# fat51p.net
KiCad netlist of a schematic drawn in Altium Designer
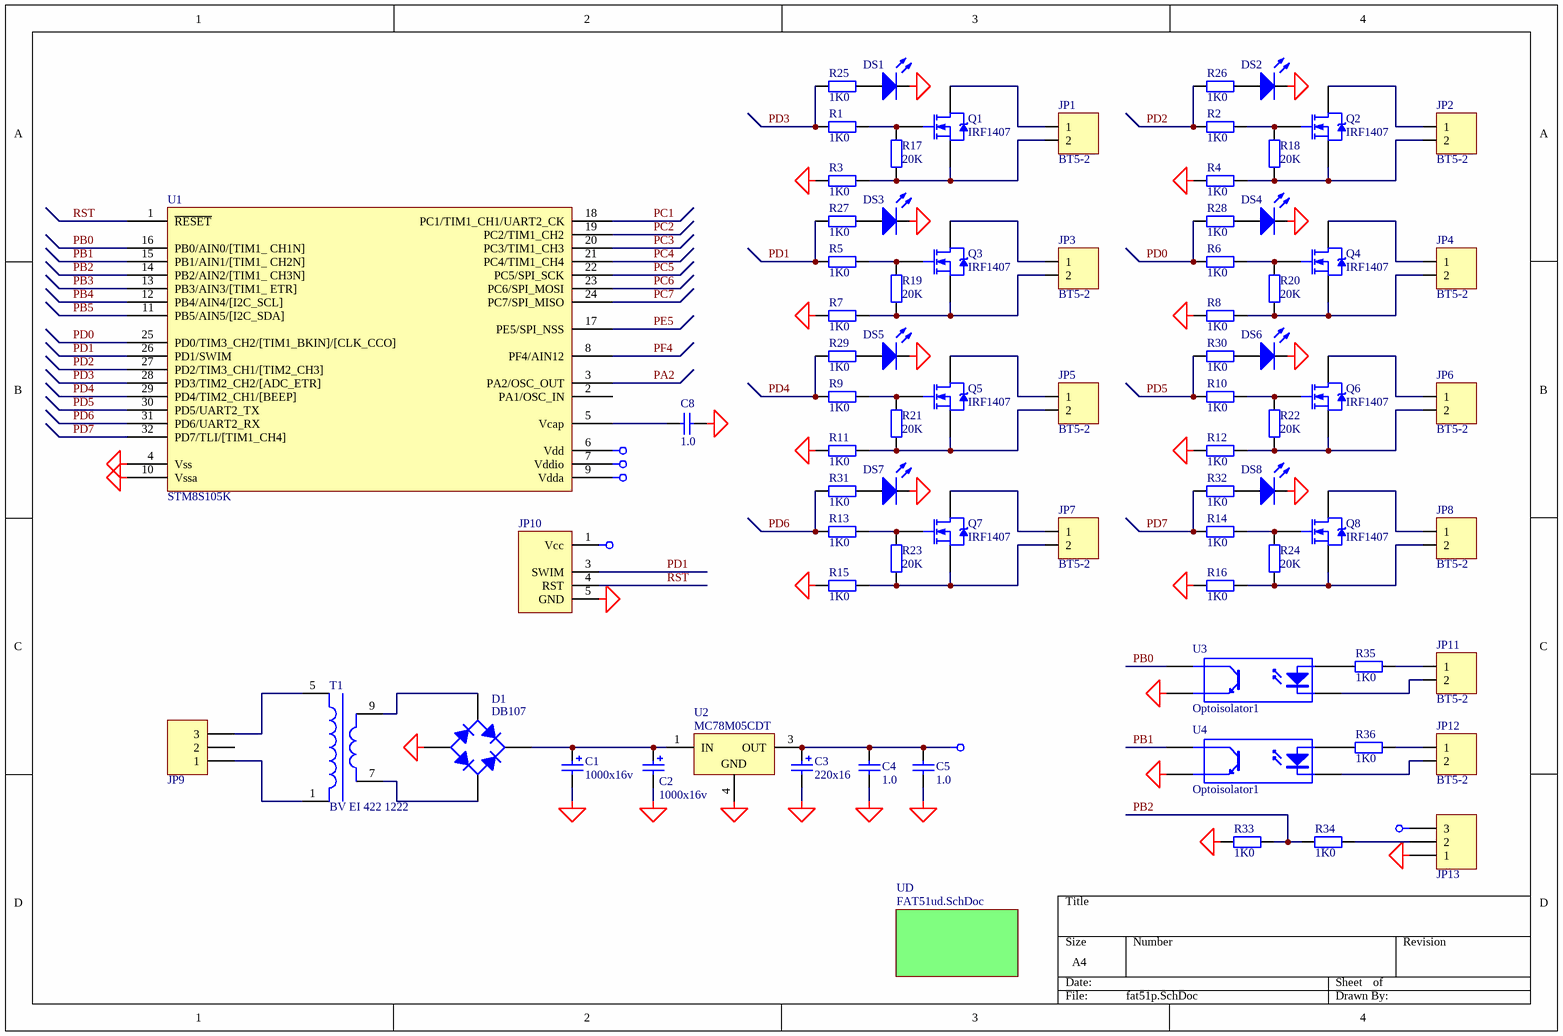
[diagram p0: fat51p.SchDoc]

(export (version "E")
  (design (tool "Eeschema 10.0.6"))
  (components
    (comp (ref "C1")
      (value "1000x16v")
      (footprint "el5")
      (description "Polarized Capacitor (Radial)")
      (fields (field (name "MANUFACTURER") "Generic Components") (field (name "PUBLISHER") "Altium Limited"))
      (libsource (lib "BUF") (part "Cap Pol1"))
    )
    (comp (ref "C2")
      (value "1000x16v")
      (footprint "el5")
      (description "Polarized Capacitor (Radial)")
      (fields (field (name "MANUFACTURER") "Generic Components") (field (name "PUBLISHER") "Altium Limited"))
      (libsource (lib "BUF") (part "Cap Pol1"))
    )
    (comp (ref "C3")
      (value "220x16")
      (footprint "el3")
      (description "Polarized Capacitor (Radial)")
      (fields (field (name "MANUFACTURER") "Generic Components") (field (name "PUBLISHER") "Altium Limited"))
      (libsource (lib "BUF") (part "Cap Pol"))
    )
    (comp (ref "C4")
      (value "Cap")
      (footprint "_1206")
      (description "Capacitor")
      (fields
        (field (name "MANUFACTURER") "Generic Components")
        (field (name "ALTIUM_VALUE") "1.0")
        (field (name "PUBLISHER") "Altium Limited")
      )
      (libsource (lib "BUF") (part "Cap"))
    )
    (comp (ref "C5")
      (value "Cap")
      (footprint "_1206")
      (description "Capacitor")
      (fields
        (field (name "MANUFACTURER") "Generic Components")
        (field (name "ALTIUM_VALUE") "1.0")
        (field (name "PUBLISHER") "Altium Limited")
      )
      (libsource (lib "BUF") (part "Cap"))
    )
    (comp (ref "C8")
      (value "1.0")
      (footprint "_1206")
      (description "Capacitor (Semiconductor SIM Model)")
      (fields (field (name "MANUFACTURER") "Generic Components") (field (name "PUBLISHER") "Altium Limited"))
      (libsource (lib "Miscellaneous Devices") (part "Cap Semi"))
    )
    (comp (ref "D1")
      (value "DB107")
      (footprint "DF01")
      (description "Full Wave Diode Bridge")
      (fields (field (name "MANUFACTURER") "Generic Components") (field (name "PUBLISHER") "Altium Limited"))
      (libsource (lib "Miscellaneous Devices") (part "Bridge1"))
    )
    (comp (ref "DS1")
      (value "LED0")
      (footprint "el3")
      (description "Typical INFRARED GaAs LED")
      (fields (field (name "MANUFACTURER") "Generic Components") (field (name "PUBLISHER") "Altium Limited"))
      (libsource (lib "PAL") (part "LED0"))
    )
    (comp (ref "DS2")
      (value "LED0")
      (footprint "el3")
      (description "Typical INFRARED GaAs LED")
      (fields (field (name "MANUFACTURER") "Generic Components") (field (name "PUBLISHER") "Altium Limited"))
      (libsource (lib "PAL") (part "LED0"))
    )
    (comp (ref "DS3")
      (value "LED0")
      (footprint "el3")
      (description "Typical INFRARED GaAs LED")
      (fields (field (name "MANUFACTURER") "Generic Components") (field (name "PUBLISHER") "Altium Limited"))
      (libsource (lib "PAL") (part "LED0"))
    )
    (comp (ref "DS4")
      (value "LED0")
      (footprint "el3")
      (description "Typical INFRARED GaAs LED")
      (fields (field (name "MANUFACTURER") "Generic Components") (field (name "PUBLISHER") "Altium Limited"))
      (libsource (lib "PAL") (part "LED0"))
    )
    (comp (ref "DS5")
      (value "LED0")
      (footprint "el3")
      (description "Typical INFRARED GaAs LED")
      (fields (field (name "MANUFACTURER") "Generic Components") (field (name "PUBLISHER") "Altium Limited"))
      (libsource (lib "PAL") (part "LED0"))
    )
    (comp (ref "DS6")
      (value "LED0")
      (footprint "el3")
      (description "Typical INFRARED GaAs LED")
      (fields (field (name "MANUFACTURER") "Generic Components") (field (name "PUBLISHER") "Altium Limited"))
      (libsource (lib "PAL") (part "LED0"))
    )
    (comp (ref "DS7")
      (value "LED0")
      (footprint "el3")
      (description "Typical INFRARED GaAs LED")
      (fields (field (name "MANUFACTURER") "Generic Components") (field (name "PUBLISHER") "Altium Limited"))
      (libsource (lib "PAL") (part "LED0"))
    )
    (comp (ref "DS8")
      (value "LED0")
      (footprint "el3")
      (description "Typical INFRARED GaAs LED")
      (fields (field (name "MANUFACTURER") "Generic Components") (field (name "PUBLISHER") "Altium Limited"))
      (libsource (lib "PAL") (part "LED0"))
    )
    (comp (ref "JP1")
      (value "BT5-2")
      (footprint "BT5-2-1")
      (description "Header, 3-Pin")
      (fields (field (name "MANUFACTURER") "Generic Components") (field (name "PUBLISHER") "Altium Limited"))
      (libsource (lib "PAL") (part "BT5-2"))
    )
    (comp (ref "JP2")
      (value "BT5-2")
      (footprint "BT5-2-1")
      (description "Header, 3-Pin")
      (fields (field (name "MANUFACTURER") "Generic Components") (field (name "PUBLISHER") "Altium Limited"))
      (libsource (lib "PAL") (part "BT5-2"))
    )
    (comp (ref "JP3")
      (value "BT5-2")
      (footprint "BT5-2-1")
      (description "Header, 3-Pin")
      (fields (field (name "MANUFACTURER") "Generic Components") (field (name "PUBLISHER") "Altium Limited"))
      (libsource (lib "PAL") (part "BT5-2"))
    )
    (comp (ref "JP4")
      (value "BT5-2")
      (footprint "BT5-2-1")
      (description "Header, 3-Pin")
      (fields (field (name "MANUFACTURER") "Generic Components") (field (name "PUBLISHER") "Altium Limited"))
      (libsource (lib "PAL") (part "BT5-2"))
    )
    (comp (ref "JP5")
      (value "BT5-2")
      (footprint "BT5-2-1")
      (description "Header, 3-Pin")
      (fields (field (name "MANUFACTURER") "Generic Components") (field (name "PUBLISHER") "Altium Limited"))
      (libsource (lib "PAL") (part "BT5-2"))
    )
    (comp (ref "JP6")
      (value "BT5-2")
      (footprint "BT5-2-1")
      (description "Header, 3-Pin")
      (fields (field (name "MANUFACTURER") "Generic Components") (field (name "PUBLISHER") "Altium Limited"))
      (libsource (lib "PAL") (part "BT5-2"))
    )
    (comp (ref "JP7")
      (value "BT5-2")
      (footprint "BT5-2-1")
      (description "Header, 3-Pin")
      (fields (field (name "MANUFACTURER") "Generic Components") (field (name "PUBLISHER") "Altium Limited"))
      (libsource (lib "PAL") (part "BT5-2"))
    )
    (comp (ref "JP8")
      (value "BT5-2")
      (footprint "BT5-2-1")
      (description "Header, 3-Pin")
      (fields (field (name "MANUFACTURER") "Generic Components") (field (name "PUBLISHER") "Altium Limited"))
      (libsource (lib "PAL") (part "BT5-2"))
    )
    (comp (ref "JP9")
      (value "Header 3")
      (footprint "BT5-3")
      (description "Header, 3-Pin")
      (fields (field (name "MANUFACTURER") "Generic Components") (field (name "PUBLISHER") "Altium Limited"))
      (libsource (lib "") (part "Header 3_1"))
    )
    (comp (ref "JP10") (value "~") (footprint "HDR1X5_uart") (libsource (lib "PAL") (part "SWIM_CONN")))
    (comp (ref "JP11")
      (value "BT5-2")
      (footprint "BT5-2-1")
      (description "Header, 3-Pin")
      (fields (field (name "MANUFACTURER") "Generic Components") (field (name "PUBLISHER") "Altium Limited"))
      (libsource (lib "PAL") (part "BT5-2"))
    )
    (comp (ref "JP12")
      (value "BT5-2")
      (footprint "BT5-2-1")
      (description "Header, 3-Pin")
      (fields (field (name "MANUFACTURER") "Generic Components") (field (name "PUBLISHER") "Altium Limited"))
      (libsource (lib "PAL") (part "BT5-2"))
    )
    (comp (ref "JP13")
      (value "Header 3")
      (footprint "BT5-3")
      (description "Header, 3-Pin")
      (fields (field (name "MANUFACTURER") "Generic Components") (field (name "PUBLISHER") "Altium Limited"))
      (libsource (lib "Miscellaneous Connectors") (part "Header 3"))
    )
    (comp (ref "Q1")
      (value "IRF1407")
      (footprint "7805_2")
      (description "HEXFET N-Channel Power MOSFET")
      (fields
        (field (name "MANUFACTURER") "International Rectifier")
        (field (name "PUBLISHER") "Altium Limited")
      )
      (libsource (lib "FAT51") (part "IRFR120"))
    )
    (comp (ref "Q2")
      (value "IRF1407")
      (footprint "7805_2")
      (description "HEXFET N-Channel Power MOSFET")
      (fields
        (field (name "MANUFACTURER") "International Rectifier")
        (field (name "PUBLISHER") "Altium Limited")
      )
      (libsource (lib "FAT51") (part "IRFR120"))
    )
    (comp (ref "Q3")
      (value "IRF1407")
      (footprint "7805_2")
      (description "HEXFET N-Channel Power MOSFET")
      (fields
        (field (name "MANUFACTURER") "International Rectifier")
        (field (name "PUBLISHER") "Altium Limited")
      )
      (libsource (lib "FAT51") (part "IRFR120"))
    )
    (comp (ref "Q4")
      (value "IRF1407")
      (footprint "7805_2")
      (description "HEXFET N-Channel Power MOSFET")
      (fields
        (field (name "MANUFACTURER") "International Rectifier")
        (field (name "PUBLISHER") "Altium Limited")
      )
      (libsource (lib "FAT51") (part "IRFR120"))
    )
    (comp (ref "Q5")
      (value "IRF1407")
      (footprint "7805_2")
      (description "HEXFET N-Channel Power MOSFET")
      (fields
        (field (name "MANUFACTURER") "International Rectifier")
        (field (name "PUBLISHER") "Altium Limited")
      )
      (libsource (lib "FAT51") (part "IRFR120"))
    )
    (comp (ref "Q6")
      (value "IRF1407")
      (footprint "7805_2")
      (description "HEXFET N-Channel Power MOSFET")
      (fields
        (field (name "MANUFACTURER") "International Rectifier")
        (field (name "PUBLISHER") "Altium Limited")
      )
      (libsource (lib "FAT51") (part "IRFR120"))
    )
    (comp (ref "Q7")
      (value "IRF1407")
      (footprint "7805_2")
      (description "HEXFET N-Channel Power MOSFET")
      (fields
        (field (name "MANUFACTURER") "International Rectifier")
        (field (name "PUBLISHER") "Altium Limited")
      )
      (libsource (lib "FAT51") (part "IRFR120"))
    )
    (comp (ref "Q8")
      (value "IRF1407")
      (footprint "7805_2")
      (description "HEXFET N-Channel Power MOSFET")
      (fields
        (field (name "MANUFACTURER") "International Rectifier")
        (field (name "PUBLISHER") "Altium Limited")
      )
      (libsource (lib "FAT51") (part "IRFR120"))
    )
    (comp (ref "R1")
      (value "1K0")
      (footprint "_1206")
      (description "Resistor")
      (fields (field (name "MANUFACTURER") "Generic Components") (field (name "PUBLISHER") "Altium Limited"))
      (libsource (lib "Miscellaneous Devices") (part "Res2"))
    )
    (comp (ref "R2")
      (value "1K0")
      (footprint "_1206")
      (description "Resistor")
      (fields (field (name "MANUFACTURER") "Generic Components") (field (name "PUBLISHER") "Altium Limited"))
      (libsource (lib "Miscellaneous Devices") (part "Res2"))
    )
    (comp (ref "R3")
      (value "1K0")
      (footprint "_1206")
      (description "Resistor")
      (fields (field (name "MANUFACTURER") "Generic Components") (field (name "PUBLISHER") "Altium Limited"))
      (libsource (lib "Miscellaneous Devices") (part "Res2"))
    )
    (comp (ref "R4")
      (value "1K0")
      (footprint "_1206")
      (description "Resistor")
      (fields (field (name "MANUFACTURER") "Generic Components") (field (name "PUBLISHER") "Altium Limited"))
      (libsource (lib "Miscellaneous Devices") (part "Res2"))
    )
    (comp (ref "R5")
      (value "1K0")
      (footprint "_1206")
      (description "Resistor")
      (fields (field (name "MANUFACTURER") "Generic Components") (field (name "PUBLISHER") "Altium Limited"))
      (libsource (lib "Miscellaneous Devices") (part "Res2"))
    )
    (comp (ref "R6")
      (value "1K0")
      (footprint "_1206")
      (description "Resistor")
      (fields (field (name "MANUFACTURER") "Generic Components") (field (name "PUBLISHER") "Altium Limited"))
      (libsource (lib "Miscellaneous Devices") (part "Res2"))
    )
    (comp (ref "R7")
      (value "1K0")
      (footprint "_1206")
      (description "Resistor")
      (fields (field (name "MANUFACTURER") "Generic Components") (field (name "PUBLISHER") "Altium Limited"))
      (libsource (lib "Miscellaneous Devices") (part "Res2"))
    )
    (comp (ref "R8")
      (value "1K0")
      (footprint "_1206")
      (description "Resistor")
      (fields (field (name "MANUFACTURER") "Generic Components") (field (name "PUBLISHER") "Altium Limited"))
      (libsource (lib "Miscellaneous Devices") (part "Res2"))
    )
    (comp (ref "R9")
      (value "1K0")
      (footprint "_1206")
      (description "Resistor")
      (fields (field (name "MANUFACTURER") "Generic Components") (field (name "PUBLISHER") "Altium Limited"))
      (libsource (lib "Miscellaneous Devices") (part "Res2"))
    )
    (comp (ref "R10")
      (value "1K0")
      (footprint "_1206")
      (description "Resistor")
      (fields (field (name "MANUFACTURER") "Generic Components") (field (name "PUBLISHER") "Altium Limited"))
      (libsource (lib "Miscellaneous Devices") (part "Res2"))
    )
    (comp (ref "R11")
      (value "1K0")
      (footprint "_1206")
      (description "Resistor")
      (fields (field (name "MANUFACTURER") "Generic Components") (field (name "PUBLISHER") "Altium Limited"))
      (libsource (lib "Miscellaneous Devices") (part "Res2"))
    )
    (comp (ref "R12")
      (value "1K0")
      (footprint "_1206")
      (description "Resistor")
      (fields (field (name "MANUFACTURER") "Generic Components") (field (name "PUBLISHER") "Altium Limited"))
      (libsource (lib "Miscellaneous Devices") (part "Res2"))
    )
    (comp (ref "R13")
      (value "1K0")
      (footprint "_1206")
      (description "Resistor")
      (fields (field (name "MANUFACTURER") "Generic Components") (field (name "PUBLISHER") "Altium Limited"))
      (libsource (lib "Miscellaneous Devices") (part "Res2"))
    )
    (comp (ref "R14")
      (value "1K0")
      (footprint "_1206")
      (description "Resistor")
      (fields (field (name "MANUFACTURER") "Generic Components") (field (name "PUBLISHER") "Altium Limited"))
      (libsource (lib "Miscellaneous Devices") (part "Res2"))
    )
    (comp (ref "R15")
      (value "1K0")
      (footprint "_1206")
      (description "Resistor")
      (fields (field (name "MANUFACTURER") "Generic Components") (field (name "PUBLISHER") "Altium Limited"))
      (libsource (lib "Miscellaneous Devices") (part "Res2"))
    )
    (comp (ref "R16")
      (value "1K0")
      (footprint "_1206")
      (description "Resistor")
      (fields (field (name "MANUFACTURER") "Generic Components") (field (name "PUBLISHER") "Altium Limited"))
      (libsource (lib "Miscellaneous Devices") (part "Res2"))
    )
    (comp (ref "R17")
      (value "20K")
      (footprint "_1206")
      (description "Resistor")
      (fields (field (name "MANUFACTURER") "Generic Components") (field (name "PUBLISHER") "Altium Limited"))
      (libsource (lib "") (part "Res2_1"))
    )
    (comp (ref "R18")
      (value "20K")
      (footprint "_1206")
      (description "Resistor")
      (fields (field (name "MANUFACTURER") "Generic Components") (field (name "PUBLISHER") "Altium Limited"))
      (libsource (lib "") (part "Res2_1"))
    )
    (comp (ref "R19")
      (value "20K")
      (footprint "_1206")
      (description "Resistor")
      (fields (field (name "MANUFACTURER") "Generic Components") (field (name "PUBLISHER") "Altium Limited"))
      (libsource (lib "") (part "Res2_1"))
    )
    (comp (ref "R20")
      (value "20K")
      (footprint "_1206")
      (description "Resistor")
      (fields (field (name "MANUFACTURER") "Generic Components") (field (name "PUBLISHER") "Altium Limited"))
      (libsource (lib "") (part "Res2_1"))
    )
    (comp (ref "R21")
      (value "20K")
      (footprint "_1206")
      (description "Resistor")
      (fields (field (name "MANUFACTURER") "Generic Components") (field (name "PUBLISHER") "Altium Limited"))
      (libsource (lib "") (part "Res2_1"))
    )
    (comp (ref "R22")
      (value "20K")
      (footprint "_1206")
      (description "Resistor")
      (fields (field (name "MANUFACTURER") "Generic Components") (field (name "PUBLISHER") "Altium Limited"))
      (libsource (lib "") (part "Res2_1"))
    )
    (comp (ref "R23")
      (value "20K")
      (footprint "_1206")
      (description "Resistor")
      (fields (field (name "MANUFACTURER") "Generic Components") (field (name "PUBLISHER") "Altium Limited"))
      (libsource (lib "") (part "Res2_1"))
    )
    (comp (ref "R24")
      (value "20K")
      (footprint "_1206")
      (description "Resistor")
      (fields (field (name "MANUFACTURER") "Generic Components") (field (name "PUBLISHER") "Altium Limited"))
      (libsource (lib "") (part "Res2_1"))
    )
    (comp (ref "R25")
      (value "1K0")
      (footprint "_1206")
      (description "Resistor")
      (fields (field (name "MANUFACTURER") "Generic Components") (field (name "PUBLISHER") "Altium Limited"))
      (libsource (lib "Miscellaneous Devices") (part "Res2"))
    )
    (comp (ref "R26")
      (value "1K0")
      (footprint "_1206")
      (description "Resistor")
      (fields (field (name "MANUFACTURER") "Generic Components") (field (name "PUBLISHER") "Altium Limited"))
      (libsource (lib "Miscellaneous Devices") (part "Res2"))
    )
    (comp (ref "R27")
      (value "1K0")
      (footprint "_1206")
      (description "Resistor")
      (fields (field (name "MANUFACTURER") "Generic Components") (field (name "PUBLISHER") "Altium Limited"))
      (libsource (lib "Miscellaneous Devices") (part "Res2"))
    )
    (comp (ref "R28")
      (value "1K0")
      (footprint "_1206")
      (description "Resistor")
      (fields (field (name "MANUFACTURER") "Generic Components") (field (name "PUBLISHER") "Altium Limited"))
      (libsource (lib "Miscellaneous Devices") (part "Res2"))
    )
    (comp (ref "R29")
      (value "1K0")
      (footprint "_1206")
      (description "Resistor")
      (fields (field (name "MANUFACTURER") "Generic Components") (field (name "PUBLISHER") "Altium Limited"))
      (libsource (lib "Miscellaneous Devices") (part "Res2"))
    )
    (comp (ref "R30")
      (value "1K0")
      (footprint "_1206")
      (description "Resistor")
      (fields (field (name "MANUFACTURER") "Generic Components") (field (name "PUBLISHER") "Altium Limited"))
      (libsource (lib "Miscellaneous Devices") (part "Res2"))
    )
    (comp (ref "R31")
      (value "1K0")
      (footprint "_1206")
      (description "Resistor")
      (fields (field (name "MANUFACTURER") "Generic Components") (field (name "PUBLISHER") "Altium Limited"))
      (libsource (lib "Miscellaneous Devices") (part "Res2"))
    )
    (comp (ref "R32")
      (value "1K0")
      (footprint "_1206")
      (description "Resistor")
      (fields (field (name "MANUFACTURER") "Generic Components") (field (name "PUBLISHER") "Altium Limited"))
      (libsource (lib "Miscellaneous Devices") (part "Res2"))
    )
    (comp (ref "R33")
      (value "1K0")
      (footprint "_1206")
      (description "Resistor")
      (fields (field (name "MANUFACTURER") "Generic Components") (field (name "PUBLISHER") "Altium Limited"))
      (libsource (lib "Miscellaneous Devices") (part "Res2"))
    )
    (comp (ref "R34")
      (value "1K0")
      (footprint "_1206")
      (description "Resistor")
      (fields (field (name "MANUFACTURER") "Generic Components") (field (name "PUBLISHER") "Altium Limited"))
      (libsource (lib "Miscellaneous Devices") (part "Res2"))
    )
    (comp (ref "R35")
      (value "1K0")
      (footprint "_1206")
      (description "Resistor")
      (fields (field (name "MANUFACTURER") "Generic Components") (field (name "PUBLISHER") "Altium Limited"))
      (libsource (lib "Miscellaneous Devices") (part "Res2"))
    )
    (comp (ref "R36")
      (value "1K0")
      (footprint "_1206")
      (description "Resistor")
      (fields (field (name "MANUFACTURER") "Generic Components") (field (name "PUBLISHER") "Altium Limited"))
      (libsource (lib "Miscellaneous Devices") (part "Res2"))
    )
    (comp (ref "T1")
      (value "BV EI 422 1222")
      (footprint "BV EI 422 1226_L")
      (fields (field (name "MANUFACTURER") "Generic Components") (field (name "PUBLISHER") "Altium Limited"))
      (libsource (lib "PAL") (part "BV EI 302"))
    )
    (comp (ref "U1")
      (value "STM8S105K")
      (footprint "QFP7X7-G32/X.5N")
      (libsource (lib "PAL") (part "STM8S105K"))
    )
    (comp (ref "U2")
      (value "MC78M05CDT")
      (footprint "SIP-G3/Z11.05")
      (description "Three-Terminal Medium Current Positive Voltage Regulator")
      (fields (field (name "MANUFACTURER") "ON Semiconductor") (field (name "PUBLISHER") "Altium Limited"))
      (libsource (lib "ON Semi Power Mgt Voltage Regulator") (part "MC78M05CDT"))
    )
    (comp (ref "U3")
      (value "Optoisolator1")
      (footprint "SO-G4")
      (description "Optoisolator")
      (fields (field (name "MANUFACTURER") "Generic Components") (field (name "PUBLISHER") "Altium Limited"))
      (libsource (lib "PAL") (part "Optoisolator1"))
    )
    (comp (ref "U4")
      (value "Optoisolator1")
      (footprint "SO-G4")
      (description "Optoisolator")
      (fields (field (name "MANUFACTURER") "Generic Components") (field (name "PUBLISHER") "Altium Limited"))
      (libsource (lib "PAL") (part "Optoisolator1"))
    )
  )
  (nets
    (net (code "1") (name "+5v") (class "Default")
      (node (ref "C3") (pin "1") (pinfunction "1_1") (pintype "passive"))
      (node (ref "C4") (pin "2") (pinfunction "2_2") (pintype "passive"))
      (node (ref "C5") (pin "2") (pinfunction "2_2") (pintype "passive"))
      (node (ref "JP10") (pin "1") (pinfunction "Vcc_1") (pintype "passive"))
      (node (ref "JP13") (pin "3") (pinfunction "3_3") (pintype "passive"))
      (node (ref "U1") (pin "6") (pinfunction "Vdd_6") (pintype "passive"))
      (node (ref "U1") (pin "7") (pinfunction "Vddio_7") (pintype "passive"))
      (node (ref "U1") (pin "9") (pinfunction "Vdda_9") (pintype "passive"))
      (node (ref "U2") (pin "3") (pinfunction "OUT_3") (pintype "power_in"))
    )
    (net (code "2") (name "/PA2") (class "Default")
      (node (ref "U1") (pin "3") (pinfunction "PA2/OSC_OUT_3") (pintype "passive"))
    )
    (net (code "3") (name "/PB0") (class "Default")
      (node (ref "U1") (pin "16") (pinfunction "PB0/AIN0/[TIM1__CH1N]_16") (pintype "passive"))
      (node (ref "U3") (pin "4") (pinfunction "C_4") (pintype "passive"))
    )
    (net (code "4") (name "/PB1") (class "Default")
      (node (ref "U1") (pin "15") (pinfunction "PB1/AIN1/[TIM1__CH2N]_15") (pintype "passive"))
      (node (ref "U4") (pin "4") (pinfunction "C_4") (pintype "passive"))
    )
    (net (code "5") (name "/PB2") (class "Default")
      (node (ref "R33") (pin "2") (pinfunction "2_2") (pintype "passive"))
      (node (ref "R34") (pin "1") (pinfunction "1_1") (pintype "passive"))
      (node (ref "U1") (pin "14") (pinfunction "PB2/AIN2/[TIM1__CH3N]_14") (pintype "passive"))
    )
    (net (code "6") (name "/PB3") (class "Default")
      (node (ref "U1") (pin "13") (pinfunction "PB3/AIN3/[TIM1__ETR]_13") (pintype "passive"))
    )
    (net (code "7") (name "/PB4") (class "Default")
      (node (ref "U1") (pin "12") (pinfunction "PB4/AIN4/[I2C_SCL]_12") (pintype "passive"))
    )
    (net (code "8") (name "/PB5") (class "Default")
      (node (ref "U1") (pin "11") (pinfunction "PB5/AIN5/[I2C_SDA]_11") (pintype "passive"))
    )
    (net (code "9") (name "/PC1") (class "Default")
      (node (ref "U1") (pin "18") (pinfunction "PC1/TIM1_CH1/UART2_CK_18") (pintype "passive"))
    )
    (net (code "10") (name "/PC2") (class "Default")
      (node (ref "U1") (pin "19") (pinfunction "PC2/TIM1_CH2_19") (pintype "passive"))
    )
    (net (code "11") (name "/PC3") (class "Default")
      (node (ref "U1") (pin "20") (pinfunction "PC3/TIM1_CH3_20") (pintype "passive"))
    )
    (net (code "12") (name "/PC4") (class "Default")
      (node (ref "U1") (pin "21") (pinfunction "PC4/TIM1_CH4_21") (pintype "passive"))
    )
    (net (code "13") (name "/PC5") (class "Default")
      (node (ref "U1") (pin "22") (pinfunction "PC5/SPI_SCK_22") (pintype "passive"))
    )
    (net (code "14") (name "/PC6") (class "Default")
      (node (ref "U1") (pin "23") (pinfunction "PC6/SPI_MOSI_23") (pintype "passive"))
    )
    (net (code "15") (name "/PC7") (class "Default")
      (node (ref "U1") (pin "24") (pinfunction "PC7/SPI_MISO_24") (pintype "passive"))
    )
    (net (code "16") (name "/PD0") (class "Default")
      (node (ref "R28") (pin "1") (pinfunction "1_1") (pintype "passive"))
      (node (ref "R6") (pin "1") (pinfunction "1_1") (pintype "passive"))
      (node (ref "U1") (pin "25") (pinfunction "PD0/TIM3_CH2/[TIM1_BKIN]/[CLK_CCO]_25") (pintype "passive"))
    )
    (net (code "17") (name "/PD1") (class "Default")
      (node (ref "JP10") (pin "3") (pinfunction "SWIM_3") (pintype "passive"))
      (node (ref "R27") (pin "1") (pinfunction "1_1") (pintype "passive"))
      (node (ref "R5") (pin "1") (pinfunction "1_1") (pintype "passive"))
      (node (ref "U1") (pin "26") (pinfunction "PD1/SWIM_26") (pintype "passive"))
    )
    (net (code "18") (name "/PD2") (class "Default")
      (node (ref "R2") (pin "1") (pinfunction "1_1") (pintype "passive"))
      (node (ref "R26") (pin "1") (pinfunction "1_1") (pintype "passive"))
      (node (ref "U1") (pin "27") (pinfunction "PD2/TIM3_CH1/[TIM2_CH3]_27") (pintype "passive"))
    )
    (net (code "19") (name "/PD3") (class "Default")
      (node (ref "R1") (pin "1") (pinfunction "1_1") (pintype "passive"))
      (node (ref "R25") (pin "1") (pinfunction "1_1") (pintype "passive"))
      (node (ref "U1") (pin "28") (pinfunction "PD3/TIM2_CH2/[ADC_ETR]_28") (pintype "passive"))
    )
    (net (code "20") (name "/PD4") (class "Default")
      (node (ref "R29") (pin "1") (pinfunction "1_1") (pintype "passive"))
      (node (ref "R9") (pin "1") (pinfunction "1_1") (pintype "passive"))
      (node (ref "U1") (pin "29") (pinfunction "PD4/TIM2_CH1/[BEEP]_29") (pintype "passive"))
    )
    (net (code "21") (name "/PD5") (class "Default")
      (node (ref "R10") (pin "1") (pinfunction "1_1") (pintype "passive"))
      (node (ref "R30") (pin "1") (pinfunction "1_1") (pintype "passive"))
      (node (ref "U1") (pin "30") (pinfunction "PD5/UART2_TX_30") (pintype "passive"))
    )
    (net (code "22") (name "/PD6") (class "Default")
      (node (ref "R13") (pin "1") (pinfunction "1_1") (pintype "passive"))
      (node (ref "R31") (pin "1") (pinfunction "1_1") (pintype "passive"))
      (node (ref "U1") (pin "31") (pinfunction "PD6/UART2_RX_31") (pintype "passive"))
    )
    (net (code "23") (name "/PD7") (class "Default")
      (node (ref "R14") (pin "1") (pinfunction "1_1") (pintype "passive"))
      (node (ref "R32") (pin "1") (pinfunction "1_1") (pintype "passive"))
      (node (ref "U1") (pin "32") (pinfunction "PD7/TLI/[TIM1_CH4]_32") (pintype "passive"))
    )
    (net (code "24") (name "/PE5") (class "Default")
      (node (ref "U1") (pin "17") (pinfunction "PE5/SPI_NSS_17") (pintype "passive"))
    )
    (net (code "25") (name "/PF4") (class "Default")
      (node (ref "U1") (pin "8") (pinfunction "PF4/AIN12_8") (pintype "passive"))
    )
    (net (code "26") (name "/RST") (class "Default")
      (node (ref "JP10") (pin "4") (pinfunction "RST_4") (pintype "passive"))
      (node (ref "U1") (pin "1") (pinfunction "~{RESET}_1") (pintype "passive"))
    )
    (net (code "27") (name "GND") (class "Default")
      (node (ref "C1") (pin "2") (pinfunction "2_2") (pintype "passive"))
      (node (ref "C2") (pin "2") (pinfunction "2_2") (pintype "passive"))
      (node (ref "C3") (pin "2") (pinfunction "2_2") (pintype "passive"))
      (node (ref "C4") (pin "1") (pinfunction "1_1") (pintype "passive"))
      (node (ref "C5") (pin "1") (pinfunction "1_1") (pintype "passive"))
      (node (ref "C8") (pin "1") (pinfunction "1_1") (pintype "passive"))
      (node (ref "D1") (pin "1") (pinfunction "A_1") (pintype "passive"))
      (node (ref "DS1") (pin "2") (pinfunction "K_2") (pintype "passive"))
      (node (ref "DS2") (pin "2") (pinfunction "K_2") (pintype "passive"))
      (node (ref "DS3") (pin "2") (pinfunction "K_2") (pintype "passive"))
      (node (ref "DS4") (pin "2") (pinfunction "K_2") (pintype "passive"))
      (node (ref "DS5") (pin "2") (pinfunction "K_2") (pintype "passive"))
      (node (ref "DS6") (pin "2") (pinfunction "K_2") (pintype "passive"))
      (node (ref "DS7") (pin "2") (pinfunction "K_2") (pintype "passive"))
      (node (ref "DS8") (pin "2") (pinfunction "K_2") (pintype "passive"))
      (node (ref "JP10") (pin "5") (pinfunction "GND_5") (pintype "passive"))
      (node (ref "JP13") (pin "1") (pinfunction "1_1") (pintype "passive"))
      (node (ref "R11") (pin "1") (pinfunction "1_1") (pintype "passive"))
      (node (ref "R12") (pin "1") (pinfunction "1_1") (pintype "passive"))
      (node (ref "R15") (pin "1") (pinfunction "1_1") (pintype "passive"))
      (node (ref "R16") (pin "1") (pinfunction "1_1") (pintype "passive"))
      (node (ref "R3") (pin "1") (pinfunction "1_1") (pintype "passive"))
      (node (ref "R33") (pin "1") (pinfunction "1_1") (pintype "passive"))
      (node (ref "R4") (pin "1") (pinfunction "1_1") (pintype "passive"))
      (node (ref "R7") (pin "1") (pinfunction "1_1") (pintype "passive"))
      (node (ref "R8") (pin "1") (pinfunction "1_1") (pintype "passive"))
      (node (ref "U1") (pin "10") (pinfunction "Vssa_10") (pintype "passive"))
      (node (ref "U1") (pin "4") (pinfunction "Vss_4") (pintype "passive"))
      (node (ref "U2") (pin "4") (pinfunction "GND_4") (pintype "power_in"))
      (node (ref "U3") (pin "3") (pinfunction "E_3") (pintype "passive"))
      (node (ref "U4") (pin "3") (pinfunction "E_3") (pintype "passive"))
    )
    (net (code "28") (name "Net-(D1-K)") (class "Default")
      (node (ref "C1") (pin "1") (pinfunction "1_1") (pintype "passive"))
      (node (ref "C2") (pin "1") (pinfunction "1_1") (pintype "passive"))
      (node (ref "D1") (pin "3") (pinfunction "K_3") (pintype "passive"))
      (node (ref "U2") (pin "1") (pinfunction "IN_1") (pintype "power_in"))
    )
    (net (code "29") (name "Net-(DS1-A)") (class "Default")
      (node (ref "DS1") (pin "1") (pinfunction "A_1") (pintype "passive"))
      (node (ref "R25") (pin "2") (pinfunction "2_2") (pintype "passive"))
    )
    (net (code "30") (name "Net-(DS2-A)") (class "Default")
      (node (ref "DS2") (pin "1") (pinfunction "A_1") (pintype "passive"))
      (node (ref "R26") (pin "2") (pinfunction "2_2") (pintype "passive"))
    )
    (net (code "31") (name "Net-(DS3-A)") (class "Default")
      (node (ref "DS3") (pin "1") (pinfunction "A_1") (pintype "passive"))
      (node (ref "R27") (pin "2") (pinfunction "2_2") (pintype "passive"))
    )
    (net (code "32") (name "Net-(DS4-A)") (class "Default")
      (node (ref "DS4") (pin "1") (pinfunction "A_1") (pintype "passive"))
      (node (ref "R28") (pin "2") (pinfunction "2_2") (pintype "passive"))
    )
    (net (code "33") (name "Net-(DS5-A)") (class "Default")
      (node (ref "DS5") (pin "1") (pinfunction "A_1") (pintype "passive"))
      (node (ref "R29") (pin "2") (pinfunction "2_2") (pintype "passive"))
    )
    (net (code "34") (name "Net-(DS6-A)") (class "Default")
      (node (ref "DS6") (pin "1") (pinfunction "A_1") (pintype "passive"))
      (node (ref "R30") (pin "2") (pinfunction "2_2") (pintype "passive"))
    )
    (net (code "35") (name "Net-(DS7-A)") (class "Default")
      (node (ref "DS7") (pin "1") (pinfunction "A_1") (pintype "passive"))
      (node (ref "R31") (pin "2") (pinfunction "2_2") (pintype "passive"))
    )
    (net (code "36") (name "Net-(DS8-A)") (class "Default")
      (node (ref "DS8") (pin "1") (pinfunction "A_1") (pintype "passive"))
      (node (ref "R32") (pin "2") (pinfunction "2_2") (pintype "passive"))
    )
    (net (code "37") (name "Net-(JP11-Pad1)") (class "Default")
      (node (ref "JP11") (pin "1") (pinfunction "1_1") (pintype "passive"))
      (node (ref "R35") (pin "2") (pinfunction "2_2") (pintype "passive"))
    )
    (net (code "38") (name "Net-(JP12-Pad1)") (class "Default")
      (node (ref "JP12") (pin "1") (pinfunction "1_1") (pintype "passive"))
      (node (ref "R36") (pin "2") (pinfunction "2_2") (pintype "passive"))
    )
    (net (code "39") (name "Net-(JP13-Pad2)") (class "Default")
      (node (ref "JP13") (pin "2") (pinfunction "2_2") (pintype "passive"))
      (node (ref "R34") (pin "2") (pinfunction "2_2") (pintype "passive"))
    )
    (net (code "40") (name "Net-(Q1-D)") (class "Default")
      (node (ref "JP1") (pin "1") (pinfunction "1_1") (pintype "passive"))
      (node (ref "Q1") (pin "2") (pinfunction "D_2") (pintype "passive"))
    )
    (net (code "41") (name "Net-(Q1-G)") (class "Default")
      (node (ref "Q1") (pin "1") (pinfunction "G_1") (pintype "passive"))
      (node (ref "R1") (pin "2") (pinfunction "2_2") (pintype "passive"))
      (node (ref "R17") (pin "1") (pinfunction "1_1") (pintype "passive"))
    )
    (net (code "42") (name "Net-(Q1-S)") (class "Default")
      (node (ref "JP1") (pin "2") (pinfunction "2_2") (pintype "passive"))
      (node (ref "Q1") (pin "3") (pinfunction "S_3") (pintype "passive"))
      (node (ref "R17") (pin "2") (pinfunction "2_2") (pintype "passive"))
      (node (ref "R3") (pin "2") (pinfunction "2_2") (pintype "passive"))
    )
    (net (code "43") (name "Net-(Q2-D)") (class "Default")
      (node (ref "JP2") (pin "1") (pinfunction "1_1") (pintype "passive"))
      (node (ref "Q2") (pin "2") (pinfunction "D_2") (pintype "passive"))
    )
    (net (code "44") (name "Net-(Q2-G)") (class "Default")
      (node (ref "Q2") (pin "1") (pinfunction "G_1") (pintype "passive"))
      (node (ref "R18") (pin "1") (pinfunction "1_1") (pintype "passive"))
      (node (ref "R2") (pin "2") (pinfunction "2_2") (pintype "passive"))
    )
    (net (code "45") (name "Net-(Q2-S)") (class "Default")
      (node (ref "JP2") (pin "2") (pinfunction "2_2") (pintype "passive"))
      (node (ref "Q2") (pin "3") (pinfunction "S_3") (pintype "passive"))
      (node (ref "R18") (pin "2") (pinfunction "2_2") (pintype "passive"))
      (node (ref "R4") (pin "2") (pinfunction "2_2") (pintype "passive"))
    )
    (net (code "46") (name "Net-(Q3-D)") (class "Default")
      (node (ref "JP3") (pin "1") (pinfunction "1_1") (pintype "passive"))
      (node (ref "Q3") (pin "2") (pinfunction "D_2") (pintype "passive"))
    )
    (net (code "47") (name "Net-(Q3-G)") (class "Default")
      (node (ref "Q3") (pin "1") (pinfunction "G_1") (pintype "passive"))
      (node (ref "R19") (pin "1") (pinfunction "1_1") (pintype "passive"))
      (node (ref "R5") (pin "2") (pinfunction "2_2") (pintype "passive"))
    )
    (net (code "48") (name "Net-(Q3-S)") (class "Default")
      (node (ref "JP3") (pin "2") (pinfunction "2_2") (pintype "passive"))
      (node (ref "Q3") (pin "3") (pinfunction "S_3") (pintype "passive"))
      (node (ref "R19") (pin "2") (pinfunction "2_2") (pintype "passive"))
      (node (ref "R7") (pin "2") (pinfunction "2_2") (pintype "passive"))
    )
    (net (code "49") (name "Net-(Q4-D)") (class "Default")
      (node (ref "JP4") (pin "1") (pinfunction "1_1") (pintype "passive"))
      (node (ref "Q4") (pin "2") (pinfunction "D_2") (pintype "passive"))
    )
    (net (code "50") (name "Net-(Q4-G)") (class "Default")
      (node (ref "Q4") (pin "1") (pinfunction "G_1") (pintype "passive"))
      (node (ref "R20") (pin "1") (pinfunction "1_1") (pintype "passive"))
      (node (ref "R6") (pin "2") (pinfunction "2_2") (pintype "passive"))
    )
    (net (code "51") (name "Net-(Q4-S)") (class "Default")
      (node (ref "JP4") (pin "2") (pinfunction "2_2") (pintype "passive"))
      (node (ref "Q4") (pin "3") (pinfunction "S_3") (pintype "passive"))
      (node (ref "R20") (pin "2") (pinfunction "2_2") (pintype "passive"))
      (node (ref "R8") (pin "2") (pinfunction "2_2") (pintype "passive"))
    )
    (net (code "52") (name "Net-(Q5-D)") (class "Default")
      (node (ref "JP5") (pin "1") (pinfunction "1_1") (pintype "passive"))
      (node (ref "Q5") (pin "2") (pinfunction "D_2") (pintype "passive"))
    )
    (net (code "53") (name "Net-(Q5-G)") (class "Default")
      (node (ref "Q5") (pin "1") (pinfunction "G_1") (pintype "passive"))
      (node (ref "R21") (pin "1") (pinfunction "1_1") (pintype "passive"))
      (node (ref "R9") (pin "2") (pinfunction "2_2") (pintype "passive"))
    )
    (net (code "54") (name "Net-(Q5-S)") (class "Default")
      (node (ref "JP5") (pin "2") (pinfunction "2_2") (pintype "passive"))
      (node (ref "Q5") (pin "3") (pinfunction "S_3") (pintype "passive"))
      (node (ref "R11") (pin "2") (pinfunction "2_2") (pintype "passive"))
      (node (ref "R21") (pin "2") (pinfunction "2_2") (pintype "passive"))
    )
    (net (code "55") (name "Net-(Q6-D)") (class "Default")
      (node (ref "JP6") (pin "1") (pinfunction "1_1") (pintype "passive"))
      (node (ref "Q6") (pin "2") (pinfunction "D_2") (pintype "passive"))
    )
    (net (code "56") (name "Net-(Q6-G)") (class "Default")
      (node (ref "Q6") (pin "1") (pinfunction "G_1") (pintype "passive"))
      (node (ref "R10") (pin "2") (pinfunction "2_2") (pintype "passive"))
      (node (ref "R22") (pin "1") (pinfunction "1_1") (pintype "passive"))
    )
    (net (code "57") (name "Net-(Q6-S)") (class "Default")
      (node (ref "JP6") (pin "2") (pinfunction "2_2") (pintype "passive"))
      (node (ref "Q6") (pin "3") (pinfunction "S_3") (pintype "passive"))
      (node (ref "R12") (pin "2") (pinfunction "2_2") (pintype "passive"))
      (node (ref "R22") (pin "2") (pinfunction "2_2") (pintype "passive"))
    )
    (net (code "58") (name "Net-(Q7-D)") (class "Default")
      (node (ref "JP7") (pin "1") (pinfunction "1_1") (pintype "passive"))
      (node (ref "Q7") (pin "2") (pinfunction "D_2") (pintype "passive"))
    )
    (net (code "59") (name "Net-(Q7-G)") (class "Default")
      (node (ref "Q7") (pin "1") (pinfunction "G_1") (pintype "passive"))
      (node (ref "R13") (pin "2") (pinfunction "2_2") (pintype "passive"))
      (node (ref "R23") (pin "1") (pinfunction "1_1") (pintype "passive"))
    )
    (net (code "60") (name "Net-(Q7-S)") (class "Default")
      (node (ref "JP7") (pin "2") (pinfunction "2_2") (pintype "passive"))
      (node (ref "Q7") (pin "3") (pinfunction "S_3") (pintype "passive"))
      (node (ref "R15") (pin "2") (pinfunction "2_2") (pintype "passive"))
      (node (ref "R23") (pin "2") (pinfunction "2_2") (pintype "passive"))
    )
    (net (code "61") (name "Net-(Q8-D)") (class "Default")
      (node (ref "JP8") (pin "1") (pinfunction "1_1") (pintype "passive"))
      (node (ref "Q8") (pin "2") (pinfunction "D_2") (pintype "passive"))
    )
    (net (code "62") (name "Net-(Q8-G)") (class "Default")
      (node (ref "Q8") (pin "1") (pinfunction "G_1") (pintype "passive"))
      (node (ref "R14") (pin "2") (pinfunction "2_2") (pintype "passive"))
      (node (ref "R24") (pin "1") (pinfunction "1_1") (pintype "passive"))
    )
    (net (code "63") (name "Net-(Q8-S)") (class "Default")
      (node (ref "JP8") (pin "2") (pinfunction "2_2") (pintype "passive"))
      (node (ref "Q8") (pin "3") (pinfunction "S_3") (pintype "passive"))
      (node (ref "R16") (pin "2") (pinfunction "2_2") (pintype "passive"))
      (node (ref "R24") (pin "2") (pinfunction "2_2") (pintype "passive"))
    )
    (net (code "64") (name "Net-(T1-Pri+)") (class "Default")
      (node (ref "JP9") (pin "1") (pinfunction "1_1") (pintype "passive"))
      (node (ref "T1") (pin "1") (pinfunction "Pri+_1") (pintype "passive"))
    )
    (net (code "65") (name "Net-(T1-Pri-)") (class "Default")
      (node (ref "JP9") (pin "3") (pinfunction "3_3") (pintype "passive"))
      (node (ref "T1") (pin "5") (pinfunction "Pri-_5") (pintype "passive"))
    )
    (net (code "66") (name "Net-(T1-Sec1+)") (class "Default")
      (node (ref "D1") (pin "4") (pinfunction "C_4") (pintype "passive"))
      (node (ref "T1") (pin "7") (pinfunction "Sec1+_7") (pintype "passive"))
    )
    (net (code "67") (name "Net-(T1-Sec1-)") (class "Default")
      (node (ref "D1") (pin "2") (pinfunction "C_2") (pintype "passive"))
      (node (ref "T1") (pin "9") (pinfunction "Sec1-_9") (pintype "passive"))
    )
    (net (code "68") (name "Net-(U1-Vcap)") (class "Default")
      (node (ref "C8") (pin "2") (pinfunction "2_2") (pintype "passive"))
      (node (ref "U1") (pin "5") (pinfunction "Vcap_5") (pintype "passive"))
    )
    (net (code "69") (name "Net-(U3-A)") (class "Default")
      (node (ref "R35") (pin "1") (pinfunction "1_1") (pintype "passive"))
      (node (ref "U3") (pin "1") (pinfunction "A_1") (pintype "passive"))
    )
    (net (code "70") (name "Net-(U3-K)") (class "Default")
      (node (ref "JP11") (pin "2") (pinfunction "2_2") (pintype "passive"))
      (node (ref "U3") (pin "2") (pinfunction "K_2") (pintype "passive"))
    )
    (net (code "71") (name "Net-(U4-A)") (class "Default")
      (node (ref "R36") (pin "1") (pinfunction "1_1") (pintype "passive"))
      (node (ref "U4") (pin "1") (pinfunction "A_1") (pintype "passive"))
    )
    (net (code "72") (name "Net-(U4-K)") (class "Default")
      (node (ref "JP12") (pin "2") (pinfunction "2_2") (pintype "passive"))
      (node (ref "U4") (pin "2") (pinfunction "K_2") (pintype "passive"))
    )
    (net (code "73") (name "unconnected-(JP9-Pad2)") (class "Default")
      (node (ref "JP9") (pin "2") (pinfunction "2_2") (pintype "passive"))
    )
    (net (code "74") (name "unconnected-(U1-PA1{slash}OSC_IN-Pad2)") (class "Default")
      (node (ref "U1") (pin "2") (pinfunction "PA1/OSC_IN_2") (pintype "passive"))
    )
  )
)
